# NeoDigito_Mini_Doble_V1.net
KiCad netlist of a schematic drawn in EAGLE
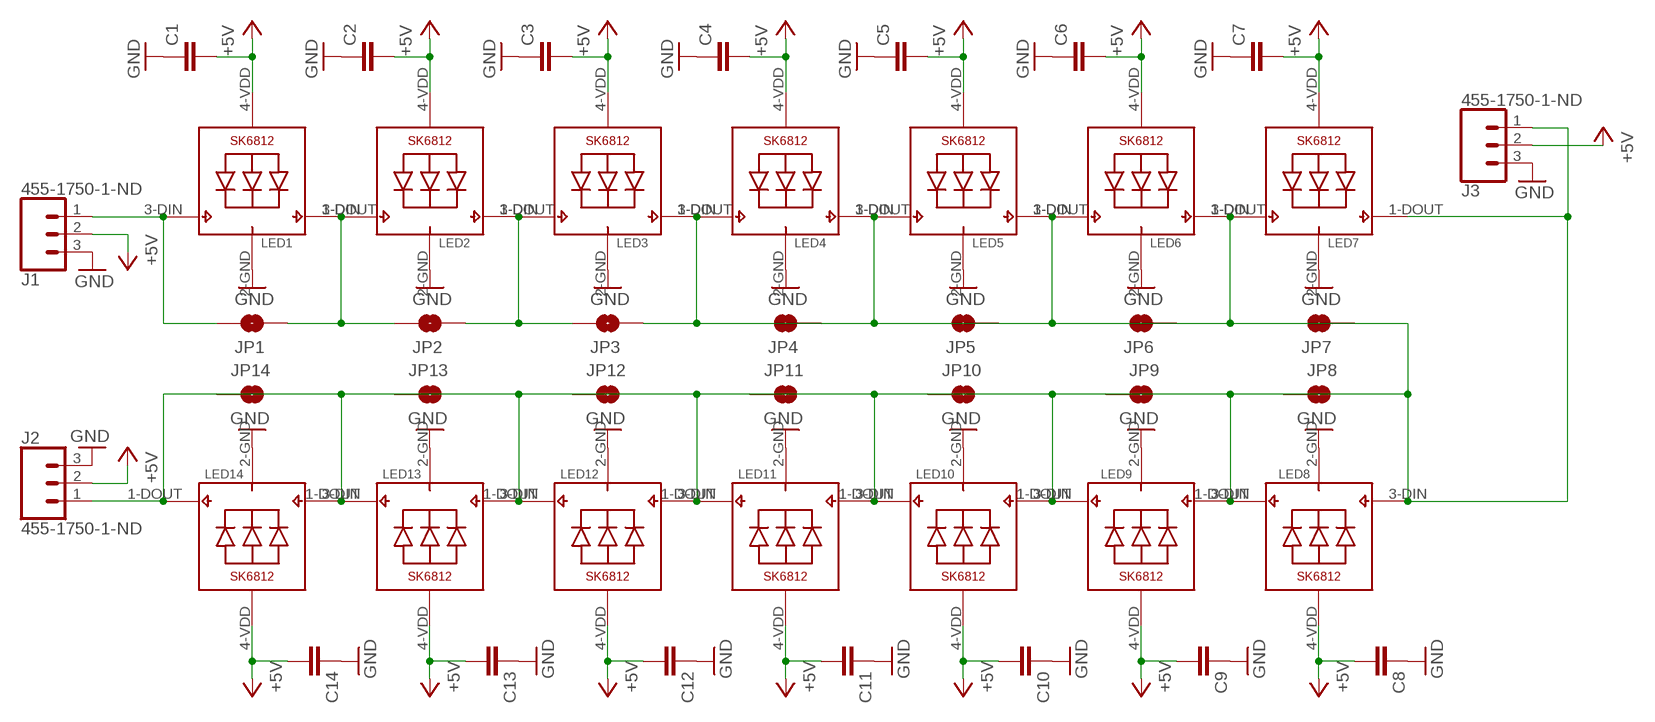
[diagram p0: schematic, sheet 1]

(export (version "E")
  (design (tool "Eeschema 10.0.6"))
  (components
    (comp (ref "C1")
      (value "C-EUC1206")
      (footprint "eagle-import:C1206")
      (libsource (lib "eagle-import") (part "C-EUC1206"))
    )
    (comp (ref "C2")
      (value "C-EUC1206")
      (footprint "eagle-import:C1206")
      (libsource (lib "eagle-import") (part "C-EUC1206"))
    )
    (comp (ref "C3")
      (value "C-EUC1206")
      (footprint "eagle-import:C1206")
      (libsource (lib "eagle-import") (part "C-EUC1206"))
    )
    (comp (ref "C4")
      (value "C-EUC1206")
      (footprint "eagle-import:C1206")
      (libsource (lib "eagle-import") (part "C-EUC1206"))
    )
    (comp (ref "C5")
      (value "C-EUC1206")
      (footprint "eagle-import:C1206")
      (libsource (lib "eagle-import") (part "C-EUC1206"))
    )
    (comp (ref "C6")
      (value "C-EUC1206")
      (footprint "eagle-import:C1206")
      (libsource (lib "eagle-import") (part "C-EUC1206"))
    )
    (comp (ref "C7")
      (value "C-EUC1206")
      (footprint "eagle-import:C1206")
      (libsource (lib "eagle-import") (part "C-EUC1206"))
    )
    (comp (ref "C8")
      (value "C-EUC1206")
      (footprint "eagle-import:C1206")
      (libsource (lib "eagle-import") (part "C-EUC1206"))
    )
    (comp (ref "C9")
      (value "C-EUC1206")
      (footprint "eagle-import:C1206")
      (libsource (lib "eagle-import") (part "C-EUC1206"))
    )
    (comp (ref "C10")
      (value "C-EUC1206")
      (footprint "eagle-import:C1206")
      (libsource (lib "eagle-import") (part "C-EUC1206"))
    )
    (comp (ref "C11")
      (value "C-EUC1206")
      (footprint "eagle-import:C1206")
      (libsource (lib "eagle-import") (part "C-EUC1206"))
    )
    (comp (ref "C12")
      (value "C-EUC1206")
      (footprint "eagle-import:C1206")
      (libsource (lib "eagle-import") (part "C-EUC1206"))
    )
    (comp (ref "C13")
      (value "C-EUC1206")
      (footprint "eagle-import:C1206")
      (libsource (lib "eagle-import") (part "C-EUC1206"))
    )
    (comp (ref "C14")
      (value "C-EUC1206")
      (footprint "eagle-import:C1206")
      (libsource (lib "eagle-import") (part "C-EUC1206"))
    )
    (comp (ref "J1")
      (value "455-1750-1-ND")
      (footprint "eagle-import:1X03")
      (libsource (lib "eagle-import") (part "CONN_03"))
    )
    (comp (ref "J2")
      (value "455-1750-1-ND")
      (footprint "eagle-import:1X03")
      (libsource (lib "eagle-import") (part "CONN_03"))
    )
    (comp (ref "J3")
      (value "455-1750-1-ND")
      (footprint "eagle-import:1X03_LONGPADS")
      (libsource (lib "eagle-import") (part "CONN_03LONGPADS"))
    )
    (comp (ref "JP1")
      (value "JUMPER-SMT_2_NO_SILK")
      (footprint "eagle-import:SMT-JUMPER_2_NO_SILK")
      (libsource (lib "eagle-import") (part "JUMPER-SMT_2_NO_SILK"))
    )
    (comp (ref "JP2")
      (value "JUMPER-SMT_2_NO_SILK")
      (footprint "eagle-import:SMT-JUMPER_2_NO_SILK")
      (libsource (lib "eagle-import") (part "JUMPER-SMT_2_NO_SILK"))
    )
    (comp (ref "JP3")
      (value "JUMPER-SMT_2_NO_SILK")
      (footprint "eagle-import:SMT-JUMPER_2_NO_SILK")
      (libsource (lib "eagle-import") (part "JUMPER-SMT_2_NO_SILK"))
    )
    (comp (ref "JP4")
      (value "JUMPER-SMT_2_NO_SILK")
      (footprint "eagle-import:SMT-JUMPER_2_NO_SILK")
      (libsource (lib "eagle-import") (part "JUMPER-SMT_2_NO_SILK"))
    )
    (comp (ref "JP5")
      (value "JUMPER-SMT_2_NO_SILK")
      (footprint "eagle-import:SMT-JUMPER_2_NO_SILK")
      (libsource (lib "eagle-import") (part "JUMPER-SMT_2_NO_SILK"))
    )
    (comp (ref "JP6")
      (value "JUMPER-SMT_2_NO_SILK")
      (footprint "eagle-import:SMT-JUMPER_2_NO_SILK")
      (libsource (lib "eagle-import") (part "JUMPER-SMT_2_NO_SILK"))
    )
    (comp (ref "JP7")
      (value "JUMPER-SMT_2_NO_SILK")
      (footprint "eagle-import:SMT-JUMPER_2_NO_SILK")
      (libsource (lib "eagle-import") (part "JUMPER-SMT_2_NO_SILK"))
    )
    (comp (ref "JP8")
      (value "JUMPER-SMT_2_NO_SILK")
      (footprint "eagle-import:SMT-JUMPER_2_NO_SILK")
      (libsource (lib "eagle-import") (part "JUMPER-SMT_2_NO_SILK"))
    )
    (comp (ref "JP9")
      (value "JUMPER-SMT_2_NO_SILK")
      (footprint "eagle-import:SMT-JUMPER_2_NO_SILK")
      (libsource (lib "eagle-import") (part "JUMPER-SMT_2_NO_SILK"))
    )
    (comp (ref "JP10")
      (value "JUMPER-SMT_2_NO_SILK")
      (footprint "eagle-import:SMT-JUMPER_2_NO_SILK")
      (libsource (lib "eagle-import") (part "JUMPER-SMT_2_NO_SILK"))
    )
    (comp (ref "JP11")
      (value "JUMPER-SMT_2_NO_SILK")
      (footprint "eagle-import:SMT-JUMPER_2_NO_SILK")
      (libsource (lib "eagle-import") (part "JUMPER-SMT_2_NO_SILK"))
    )
    (comp (ref "JP12")
      (value "JUMPER-SMT_2_NO_SILK")
      (footprint "eagle-import:SMT-JUMPER_2_NO_SILK")
      (libsource (lib "eagle-import") (part "JUMPER-SMT_2_NO_SILK"))
    )
    (comp (ref "JP13")
      (value "JUMPER-SMT_2_NO_SILK")
      (footprint "eagle-import:SMT-JUMPER_2_NO_SILK")
      (libsource (lib "eagle-import") (part "JUMPER-SMT_2_NO_SILK"))
    )
    (comp (ref "JP14")
      (value "JUMPER-SMT_2_NO_SILK")
      (footprint "eagle-import:SMT-JUMPER_2_NO_SILK")
      (libsource (lib "eagle-import") (part "JUMPER-SMT_2_NO_SILK"))
    )
    (comp (ref "LED1")
      (value "SK6812_3535")
      (footprint "eagle-import:LED3535")
      (libsource (lib "eagle-import") (part "SK6812_3535"))
    )
    (comp (ref "LED2")
      (value "SK6812_3535")
      (footprint "eagle-import:LED3535")
      (libsource (lib "eagle-import") (part "SK6812_3535"))
    )
    (comp (ref "LED3")
      (value "SK6812_3535")
      (footprint "eagle-import:LED3535")
      (libsource (lib "eagle-import") (part "SK6812_3535"))
    )
    (comp (ref "LED4")
      (value "SK6812_3535")
      (footprint "eagle-import:LED3535")
      (libsource (lib "eagle-import") (part "SK6812_3535"))
    )
    (comp (ref "LED5")
      (value "SK6812_3535")
      (footprint "eagle-import:LED3535")
      (libsource (lib "eagle-import") (part "SK6812_3535"))
    )
    (comp (ref "LED6")
      (value "SK6812_3535")
      (footprint "eagle-import:LED3535")
      (libsource (lib "eagle-import") (part "SK6812_3535"))
    )
    (comp (ref "LED7")
      (value "SK6812_3535")
      (footprint "eagle-import:LED3535")
      (libsource (lib "eagle-import") (part "SK6812_3535"))
    )
    (comp (ref "LED8")
      (value "SK6812_3535")
      (footprint "eagle-import:LED3535")
      (libsource (lib "eagle-import") (part "SK6812_3535"))
    )
    (comp (ref "LED9")
      (value "SK6812_3535")
      (footprint "eagle-import:LED3535")
      (libsource (lib "eagle-import") (part "SK6812_3535"))
    )
    (comp (ref "LED10")
      (value "SK6812_3535")
      (footprint "eagle-import:LED3535")
      (libsource (lib "eagle-import") (part "SK6812_3535"))
    )
    (comp (ref "LED11")
      (value "SK6812_3535")
      (footprint "eagle-import:LED3535")
      (libsource (lib "eagle-import") (part "SK6812_3535"))
    )
    (comp (ref "LED12")
      (value "SK6812_3535")
      (footprint "eagle-import:LED3535")
      (libsource (lib "eagle-import") (part "SK6812_3535"))
    )
    (comp (ref "LED13")
      (value "SK6812_3535")
      (footprint "eagle-import:LED3535")
      (libsource (lib "eagle-import") (part "SK6812_3535"))
    )
    (comp (ref "LED14")
      (value "SK6812_3535")
      (footprint "eagle-import:LED3535")
      (libsource (lib "eagle-import") (part "SK6812_3535"))
    )
  )
  (nets
    (net (code "1") (name "+5V") (class "Default")
      (node (ref "C1") (pin "2") (pinfunction "2_2") (pintype "passive"))
      (node (ref "C10") (pin "2") (pinfunction "2_2") (pintype "passive"))
      (node (ref "C11") (pin "2") (pinfunction "2_2") (pintype "passive"))
      (node (ref "C12") (pin "2") (pinfunction "2_2") (pintype "passive"))
      (node (ref "C13") (pin "2") (pinfunction "2_2") (pintype "passive"))
      (node (ref "C14") (pin "2") (pinfunction "2_2") (pintype "passive"))
      (node (ref "C2") (pin "2") (pinfunction "2_2") (pintype "passive"))
      (node (ref "C3") (pin "2") (pinfunction "2_2") (pintype "passive"))
      (node (ref "C4") (pin "2") (pinfunction "2_2") (pintype "passive"))
      (node (ref "C5") (pin "2") (pinfunction "2_2") (pintype "passive"))
      (node (ref "C6") (pin "2") (pinfunction "2_2") (pintype "passive"))
      (node (ref "C7") (pin "2") (pinfunction "2_2") (pintype "passive"))
      (node (ref "C8") (pin "2") (pinfunction "2_2") (pintype "passive"))
      (node (ref "C9") (pin "2") (pinfunction "2_2") (pintype "passive"))
      (node (ref "J1") (pin "2") (pinfunction "2_2") (pintype "passive"))
      (node (ref "J2") (pin "2") (pinfunction "2_2") (pintype "passive"))
      (node (ref "J3") (pin "2") (pinfunction "2_2") (pintype "passive"))
      (node (ref "LED1") (pin "4-VDD") (pinfunction "VDD_4-VDD") (pintype "power_in"))
      (node (ref "LED10") (pin "4-VDD") (pinfunction "VDD_4-VDD") (pintype "power_in"))
      (node (ref "LED11") (pin "4-VDD") (pinfunction "VDD_4-VDD") (pintype "power_in"))
      (node (ref "LED12") (pin "4-VDD") (pinfunction "VDD_4-VDD") (pintype "power_in"))
      (node (ref "LED13") (pin "4-VDD") (pinfunction "VDD_4-VDD") (pintype "power_in"))
      (node (ref "LED14") (pin "4-VDD") (pinfunction "VDD_4-VDD") (pintype "power_in"))
      (node (ref "LED2") (pin "4-VDD") (pinfunction "VDD_4-VDD") (pintype "power_in"))
      (node (ref "LED3") (pin "4-VDD") (pinfunction "VDD_4-VDD") (pintype "power_in"))
      (node (ref "LED4") (pin "4-VDD") (pinfunction "VDD_4-VDD") (pintype "power_in"))
      (node (ref "LED5") (pin "4-VDD") (pinfunction "VDD_4-VDD") (pintype "power_in"))
      (node (ref "LED6") (pin "4-VDD") (pinfunction "VDD_4-VDD") (pintype "power_in"))
      (node (ref "LED7") (pin "4-VDD") (pinfunction "VDD_4-VDD") (pintype "power_in"))
      (node (ref "LED8") (pin "4-VDD") (pinfunction "VDD_4-VDD") (pintype "power_in"))
      (node (ref "LED9") (pin "4-VDD") (pinfunction "VDD_4-VDD") (pintype "power_in"))
    )
    (net (code "2") (name "GND") (class "Default")
      (node (ref "C1") (pin "1") (pinfunction "1_1") (pintype "passive"))
      (node (ref "C10") (pin "1") (pinfunction "1_1") (pintype "passive"))
      (node (ref "C11") (pin "1") (pinfunction "1_1") (pintype "passive"))
      (node (ref "C12") (pin "1") (pinfunction "1_1") (pintype "passive"))
      (node (ref "C13") (pin "1") (pinfunction "1_1") (pintype "passive"))
      (node (ref "C14") (pin "1") (pinfunction "1_1") (pintype "passive"))
      (node (ref "C2") (pin "1") (pinfunction "1_1") (pintype "passive"))
      (node (ref "C3") (pin "1") (pinfunction "1_1") (pintype "passive"))
      (node (ref "C4") (pin "1") (pinfunction "1_1") (pintype "passive"))
      (node (ref "C5") (pin "1") (pinfunction "1_1") (pintype "passive"))
      (node (ref "C6") (pin "1") (pinfunction "1_1") (pintype "passive"))
      (node (ref "C7") (pin "1") (pinfunction "1_1") (pintype "passive"))
      (node (ref "C8") (pin "1") (pinfunction "1_1") (pintype "passive"))
      (node (ref "C9") (pin "1") (pinfunction "1_1") (pintype "passive"))
      (node (ref "J1") (pin "3") (pinfunction "3_3") (pintype "passive"))
      (node (ref "J2") (pin "3") (pinfunction "3_3") (pintype "passive"))
      (node (ref "J3") (pin "3") (pinfunction "3_3") (pintype "passive"))
      (node (ref "LED1") (pin "2-GND") (pinfunction "GND_2-GND") (pintype "power_in"))
      (node (ref "LED10") (pin "2-GND") (pinfunction "GND_2-GND") (pintype "power_in"))
      (node (ref "LED11") (pin "2-GND") (pinfunction "GND_2-GND") (pintype "power_in"))
      (node (ref "LED12") (pin "2-GND") (pinfunction "GND_2-GND") (pintype "power_in"))
      (node (ref "LED13") (pin "2-GND") (pinfunction "GND_2-GND") (pintype "power_in"))
      (node (ref "LED14") (pin "2-GND") (pinfunction "GND_2-GND") (pintype "power_in"))
      (node (ref "LED2") (pin "2-GND") (pinfunction "GND_2-GND") (pintype "power_in"))
      (node (ref "LED3") (pin "2-GND") (pinfunction "GND_2-GND") (pintype "power_in"))
      (node (ref "LED4") (pin "2-GND") (pinfunction "GND_2-GND") (pintype "power_in"))
      (node (ref "LED5") (pin "2-GND") (pinfunction "GND_2-GND") (pintype "power_in"))
      (node (ref "LED6") (pin "2-GND") (pinfunction "GND_2-GND") (pintype "power_in"))
      (node (ref "LED7") (pin "2-GND") (pinfunction "GND_2-GND") (pintype "power_in"))
      (node (ref "LED8") (pin "2-GND") (pinfunction "GND_2-GND") (pintype "power_in"))
      (node (ref "LED9") (pin "2-GND") (pinfunction "GND_2-GND") (pintype "power_in"))
    )
    (net (code "3") (name "Net-(LED1-DI)") (class "Default")
      (node (ref "J1") (pin "1") (pinfunction "1_1") (pintype "passive"))
      (node (ref "JP1") (pin "1") (pinfunction "1_1") (pintype "passive"))
      (node (ref "LED1") (pin "3-DIN") (pinfunction "DI_3-DIN") (pintype "input"))
    )
    (net (code "4") (name "Net-(LED1-DO)") (class "Default")
      (node (ref "JP1") (pin "2") (pinfunction "2_2") (pintype "passive"))
      (node (ref "JP2") (pin "1") (pinfunction "1_1") (pintype "passive"))
      (node (ref "LED1") (pin "1-DOUT") (pinfunction "DO_1-DOUT") (pintype "output"))
      (node (ref "LED2") (pin "3-DIN") (pinfunction "DI_3-DIN") (pintype "input"))
    )
    (net (code "5") (name "Net-(LED2-DO)") (class "Default")
      (node (ref "JP2") (pin "2") (pinfunction "2_2") (pintype "passive"))
      (node (ref "JP3") (pin "1") (pinfunction "1_1") (pintype "passive"))
      (node (ref "LED2") (pin "1-DOUT") (pinfunction "DO_1-DOUT") (pintype "output"))
      (node (ref "LED3") (pin "3-DIN") (pinfunction "DI_3-DIN") (pintype "input"))
    )
    (net (code "6") (name "Net-(LED3-DO)") (class "Default")
      (node (ref "JP3") (pin "2") (pinfunction "2_2") (pintype "passive"))
      (node (ref "JP4") (pin "2") (pinfunction "2_2") (pintype "passive"))
      (node (ref "LED3") (pin "1-DOUT") (pinfunction "DO_1-DOUT") (pintype "output"))
      (node (ref "LED4") (pin "3-DIN") (pinfunction "DI_3-DIN") (pintype "input"))
    )
    (net (code "7") (name "Net-(LED4-DO)") (class "Default")
      (node (ref "JP4") (pin "1") (pinfunction "1_1") (pintype "passive"))
      (node (ref "JP5") (pin "2") (pinfunction "2_2") (pintype "passive"))
      (node (ref "LED4") (pin "1-DOUT") (pinfunction "DO_1-DOUT") (pintype "output"))
      (node (ref "LED5") (pin "3-DIN") (pinfunction "DI_3-DIN") (pintype "input"))
    )
    (net (code "8") (name "Net-(LED5-DO)") (class "Default")
      (node (ref "JP5") (pin "1") (pinfunction "1_1") (pintype "passive"))
      (node (ref "JP6") (pin "2") (pinfunction "2_2") (pintype "passive"))
      (node (ref "LED5") (pin "1-DOUT") (pinfunction "DO_1-DOUT") (pintype "output"))
      (node (ref "LED6") (pin "3-DIN") (pinfunction "DI_3-DIN") (pintype "input"))
    )
    (net (code "9") (name "Net-(LED6-DO)") (class "Default")
      (node (ref "JP6") (pin "1") (pinfunction "1_1") (pintype "passive"))
      (node (ref "JP7") (pin "2") (pinfunction "2_2") (pintype "passive"))
      (node (ref "LED6") (pin "1-DOUT") (pinfunction "DO_1-DOUT") (pintype "output"))
      (node (ref "LED7") (pin "3-DIN") (pinfunction "DI_3-DIN") (pintype "input"))
    )
    (net (code "10") (name "Net-(LED7-DO)") (class "Default")
      (node (ref "J3") (pin "1") (pinfunction "1_1") (pintype "passive"))
      (node (ref "JP7") (pin "1") (pinfunction "1_1") (pintype "passive"))
      (node (ref "JP8") (pin "2") (pinfunction "2_2") (pintype "passive"))
      (node (ref "LED7") (pin "1-DOUT") (pinfunction "DO_1-DOUT") (pintype "output"))
      (node (ref "LED8") (pin "3-DIN") (pinfunction "DI_3-DIN") (pintype "input"))
    )
    (net (code "11") (name "Net-(LED8-DO)") (class "Default")
      (node (ref "JP8") (pin "1") (pinfunction "1_1") (pintype "passive"))
      (node (ref "JP9") (pin "2") (pinfunction "2_2") (pintype "passive"))
      (node (ref "LED8") (pin "1-DOUT") (pinfunction "DO_1-DOUT") (pintype "output"))
      (node (ref "LED9") (pin "3-DIN") (pinfunction "DI_3-DIN") (pintype "input"))
    )
    (net (code "12") (name "Net-(LED10-DI)") (class "Default")
      (node (ref "JP10") (pin "2") (pinfunction "2_2") (pintype "passive"))
      (node (ref "JP9") (pin "1") (pinfunction "1_1") (pintype "passive"))
      (node (ref "LED10") (pin "3-DIN") (pinfunction "DI_3-DIN") (pintype "input"))
      (node (ref "LED9") (pin "1-DOUT") (pinfunction "DO_1-DOUT") (pintype "output"))
    )
    (net (code "13") (name "Net-(LED10-DO)") (class "Default")
      (node (ref "JP10") (pin "1") (pinfunction "1_1") (pintype "passive"))
      (node (ref "JP11") (pin "2") (pinfunction "2_2") (pintype "passive"))
      (node (ref "LED10") (pin "1-DOUT") (pinfunction "DO_1-DOUT") (pintype "output"))
      (node (ref "LED11") (pin "3-DIN") (pinfunction "DI_3-DIN") (pintype "input"))
    )
    (net (code "14") (name "Net-(LED11-DO)") (class "Default")
      (node (ref "JP11") (pin "1") (pinfunction "1_1") (pintype "passive"))
      (node (ref "JP12") (pin "2") (pinfunction "2_2") (pintype "passive"))
      (node (ref "LED11") (pin "1-DOUT") (pinfunction "DO_1-DOUT") (pintype "output"))
      (node (ref "LED12") (pin "3-DIN") (pinfunction "DI_3-DIN") (pintype "input"))
    )
    (net (code "15") (name "Net-(LED12-DO)") (class "Default")
      (node (ref "JP12") (pin "1") (pinfunction "1_1") (pintype "passive"))
      (node (ref "JP13") (pin "2") (pinfunction "2_2") (pintype "passive"))
      (node (ref "LED12") (pin "1-DOUT") (pinfunction "DO_1-DOUT") (pintype "output"))
      (node (ref "LED13") (pin "3-DIN") (pinfunction "DI_3-DIN") (pintype "input"))
    )
    (net (code "16") (name "Net-(LED13-DO)") (class "Default")
      (node (ref "JP13") (pin "1") (pinfunction "1_1") (pintype "passive"))
      (node (ref "JP14") (pin "2") (pinfunction "2_2") (pintype "passive"))
      (node (ref "LED13") (pin "1-DOUT") (pinfunction "DO_1-DOUT") (pintype "output"))
      (node (ref "LED14") (pin "3-DIN") (pinfunction "DI_3-DIN") (pintype "input"))
    )
    (net (code "17") (name "Net-(LED14-DO)") (class "Default")
      (node (ref "J2") (pin "1") (pinfunction "1_1") (pintype "passive"))
      (node (ref "JP14") (pin "1") (pinfunction "1_1") (pintype "passive"))
      (node (ref "LED14") (pin "1-DOUT") (pinfunction "DO_1-DOUT") (pintype "output"))
    )
  )
)
